# Eload_Gen_3_Power_Module.net
KiCad netlist of a schematic drawn in Altium Designer
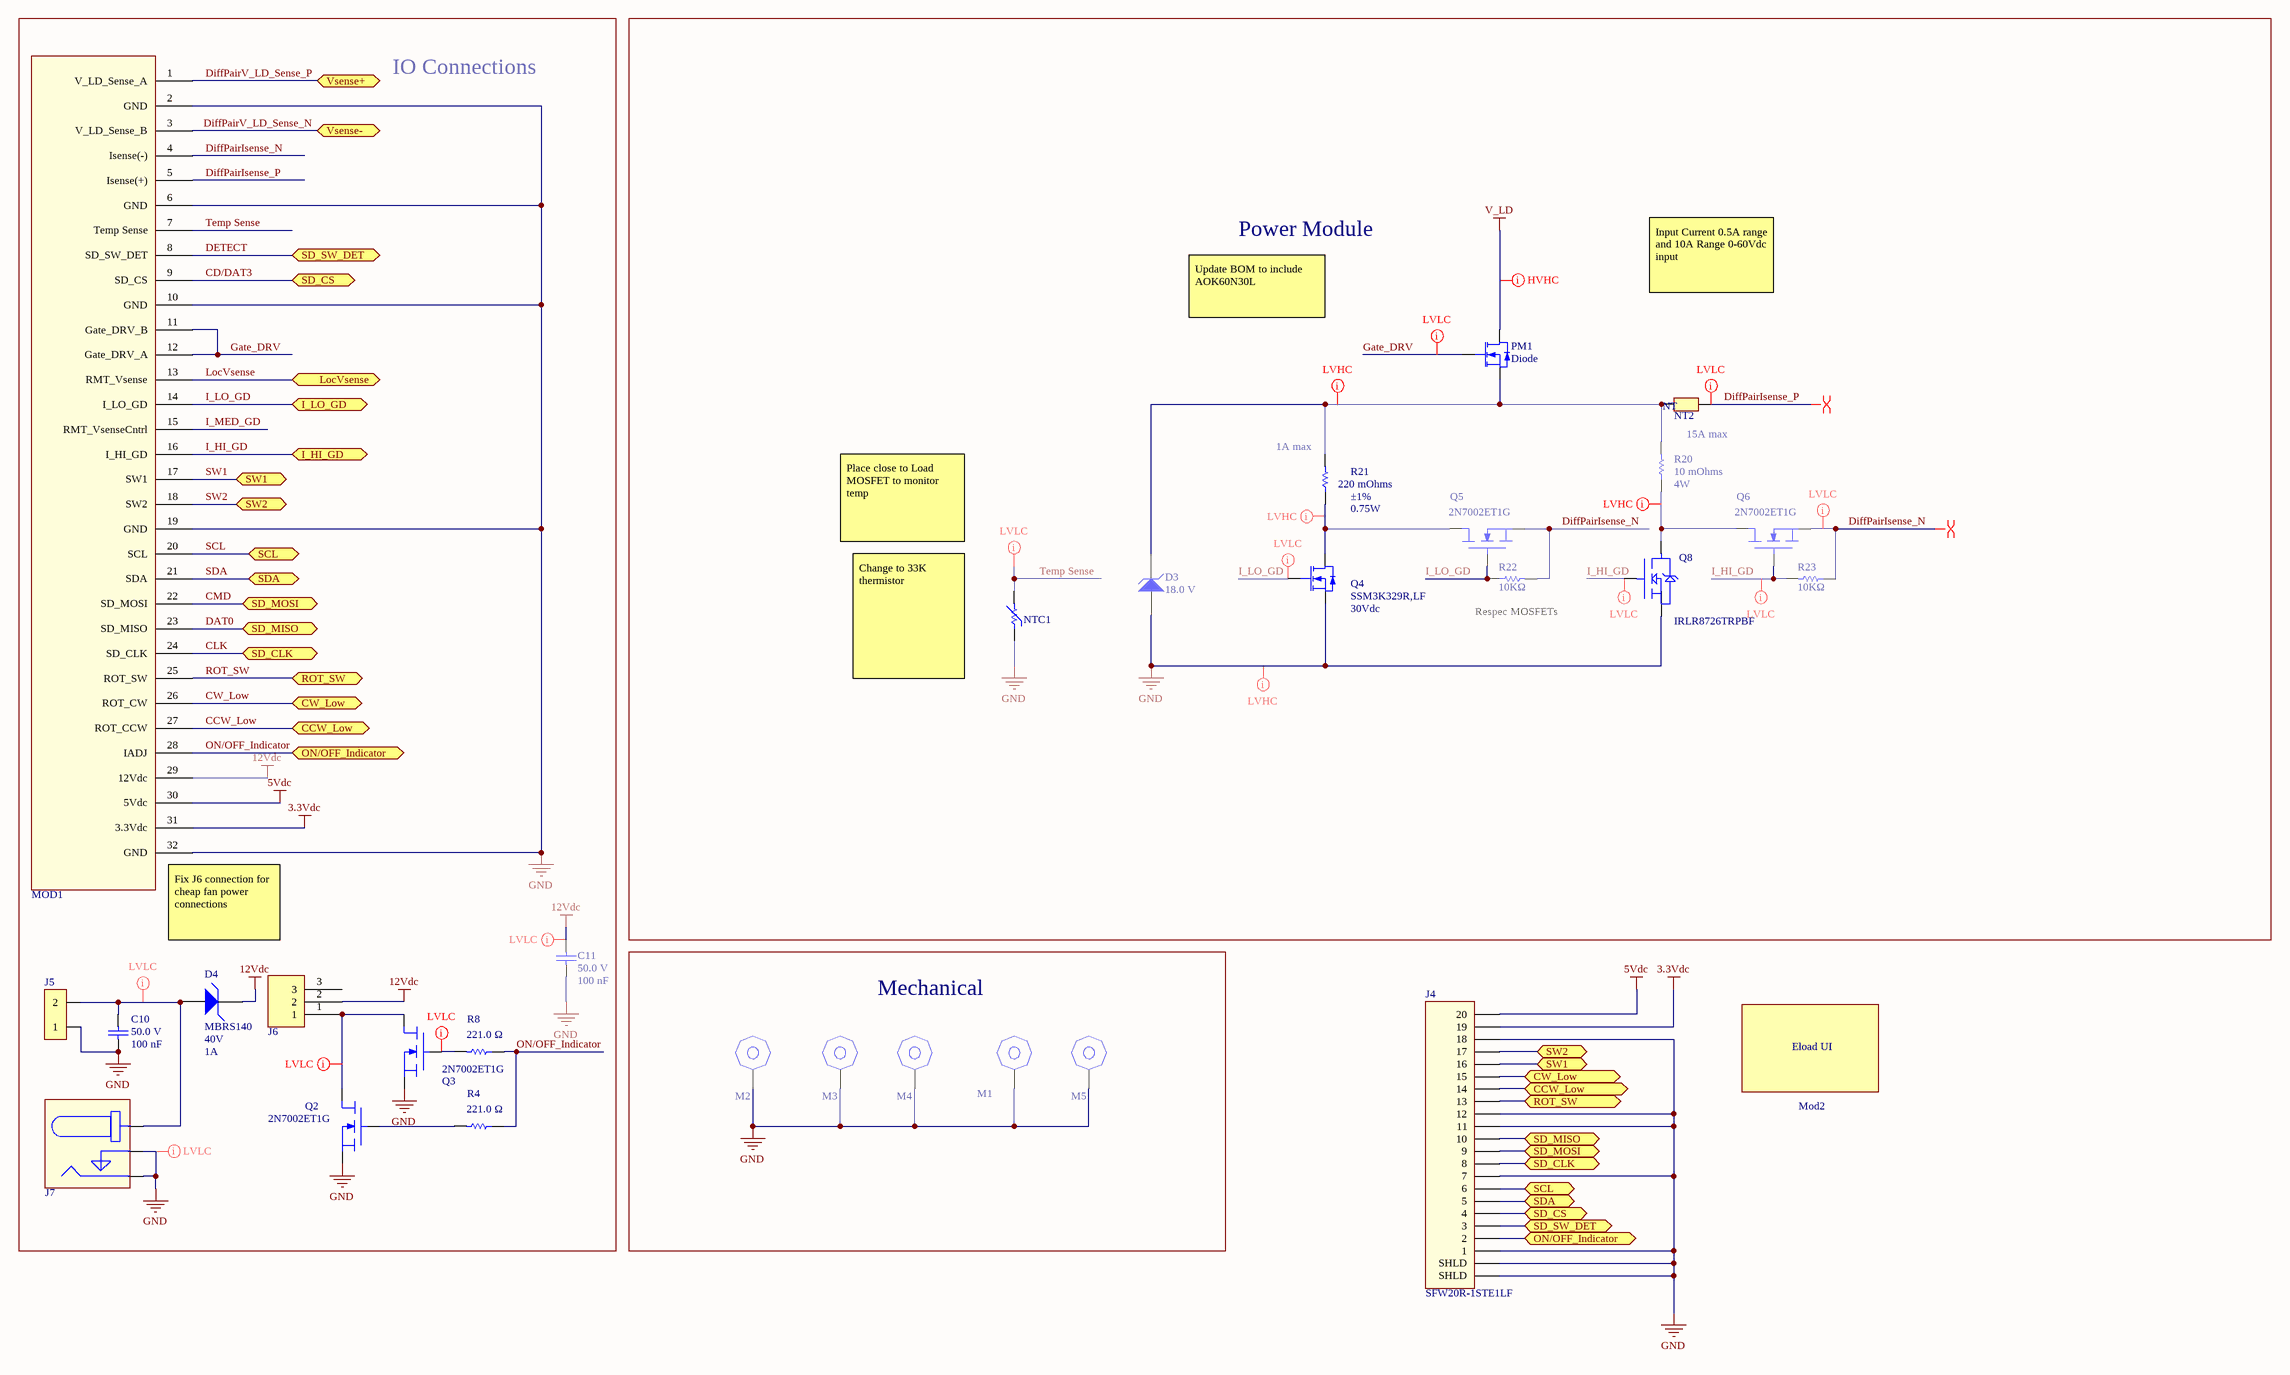
[diagram p0: Eload Gen 3 Power Module.SchDoc]

(export (version "E")
  (design (tool "Eeschema 10.0.6"))
  (components
    (comp (ref "C10")
      (value "08055C104JAT2A")
      (footprint "Cap,0805")
      (description "Capacitor; Ceramic; Cap 0.1 uF; Tol 5%; Vol-Rtg 50 VDC; SMT; 0805; X7R; Tape & Reel")
      (fields (field (name "VOLTAGE RATING (DC)") "50.0 V") (field (name "CAPACITANCE") "100 nF"))
      (libsource (lib "Master JULY2019") (part "Cap,0805,100nf,50V,5%,08055C104JAT2A"))
    )
    (comp (ref "C11")
      (value "08055C104JAT2A")
      (footprint "Cap,0805")
      (description "Capacitor; Ceramic; Cap 0.1 uF; Tol 5%; Vol-Rtg 50 VDC; SMT; 0805; X7R; Tape & Reel")
      (fields (field (name "VOLTAGE RATING (DC)") "50.0 V") (field (name "CAPACITANCE") "100 nF"))
      (libsource (lib "Master JULY2019") (part "Cap,0805,100nf,50V,5%,08055C104JAT2A"))
    )
    (comp (ref "D3")
      (value "MMSZ4705T1G")
      (footprint "SOD123")
      (description "Zener Diode 18V 500mW ±5% Surface Mount SOD-123")
      (fields (field (name "MANUFACTURER") "ON Semiconductor") (field (name "VOLTAGE RATING (DC)") "18.0 V"))
      (libsource (lib "Master JULY2019") (part "diode,Zener, 18V,500mW, SOD123,MMSZ4705T1G"))
    )
    (comp (ref "D4")
      (value "MBRS140")
      (footprint "DO214AA")
      (description "DIODE SCHOTTKY 40V 1A SMB")
      (fields
        (field (name "MANUFACTURER") "ON Semiconductor")
        (field (name "MFG P/N") "MBRS140")
        (field (name "VOLTAGE - DC REVERSE (VR) (MAX)") "40V")
        (field (name "CURRENT - AVERAGE RECTIFIED (IO)") "1A")
      )
      (libsource (lib "Master JULY2019") (part "Diode,Schottky,40V,1A,SMB,MBRS140"))
    )
    (comp (ref "J4")
      (value "SFW20R-1STE1LF")
      (footprint "Connector,FlatFlex,20Pin,RA")
      (description "CONN FFC BOTTOM 20POS 1.00MM R/A")
      (fields (field (name "MANUFACTURER") "Amphenol ICC (FCI)"))
      (libsource (lib "Master JULY2019") (part "Connector,FFC,SMD,20Pin,1mmSpc,SFW20R-1STE1LF"))
    )
    (comp (ref "J5")
      (value "TE Connectivity 282836-2")
      (footprint "TERM BLOCK 2POS SIDE ENTRY 5MM")
      (description "Wire to Board 2 Position 5 mm Pitch 30-16 AWG Euro Style Terminal Block")
      (fields (field (name "MANUFACTURER PART NUMBER") "282836-2"))
      (libsource (lib "Master JULY2019") (part "TERM BLOCK 2POS SIDE ENTRY 5MM, 282836-2"))
    )
    (comp (ref "J6")
      (value "2-644861-3")
      (footprint "Connector,TE,3-Pin,Male,Vert,2-644861-3")
      (description "Connector Header Through Hole 3 position 0.100\" (2.54mm)")
      (libsource (lib "Master JULY2019") (part "Conntector, though hole, TE, 3pin, 2.54mm,2-644861-3"))
    )
    (comp (ref "J7")
      (value "PJ-002A")
      (footprint "Connector,Barrel,2.1mm,5.5mm,DC power Jack")
      (description "Power Barrel Connector Jack 2.10mm ID (0.083\"), 5.50mm OD (0.217\") Through Hole, Right Angle")
      (fields (field (name "MANUFACTURER") "CUI Inc."))
      (libsource (lib "Master JULY2019") (part "Connector,Barrel,ID 2.1mm,OD 5.5mm,Power Connect, PJ-002A"))
    )
    (comp (ref "M1")
      (value "M3 hex Standoff")
      (footprint "Standoff,Hex,M3,8mm")
      (description "HEX STANDOFF M3,generic")
      (libsource (lib "Master Oct28_2018") (part "Standoff, M3, Hex"))
    )
    (comp (ref "M2")
      (value "M3 hex Standoff")
      (footprint "Standoff,Hex,M3,8mm")
      (description "HEX STANDOFF M3,generic")
      (libsource (lib "Master Oct28_2018") (part "Standoff, M3, Hex"))
    )
    (comp (ref "M3")
      (value "M3 hex Standoff")
      (footprint "Standoff,Hex,M3,8mm")
      (description "HEX STANDOFF M3,generic")
      (libsource (lib "Master Oct28_2018") (part "Standoff, M3, Hex"))
    )
    (comp (ref "M4")
      (value "M3 hex Standoff")
      (footprint "Standoff,Hex,M3,8mm")
      (description "HEX STANDOFF M3,generic")
      (libsource (lib "Master Oct28_2018") (part "Standoff, M3, Hex"))
    )
    (comp (ref "M5")
      (value "M3 hex Standoff")
      (footprint "Standoff,Hex,M3,8mm")
      (description "HEX STANDOFF M3,generic")
      (libsource (lib "Master Oct28_2018") (part "Standoff, M3, Hex"))
    )
    (comp (ref "MOD1")
      (value "Support PCBA")
      (footprint "Mod,ELoad Gen 3 Rev 1 Support")
      (description "Mod,Eload Gen 3 Control rev 1")
      (libsource (lib "Master JULY2019") (part "Mod,Eload Gen 3 Control rev 1"))
    )
    (comp (ref "Mod2")
      (value "ELoad Gen 3 - User Interface - Rev 1")
      (footprint "Mod,Eload Gen 3- UI Rev 1 - Vertical")
      (description "Mod, ELoad Gen 3 - User Interface - Rev 1")
      (libsource (lib "Master JULY2019") (part "Mod,Eload Gen 3 - USER INTERFACE - Rev 1"))
    )
    (comp (ref "NT2")
      (value "Net Tie,0.254mm")
      (footprint "0.254mm Net Tie")
      (libsource (lib "Master Mar2021") (part "Net Tie,0.254mm"))
    )
    (comp (ref "NTC1")
      (value "NTCLE100E3333JB0")
      (footprint "NTC,TH,2.54mm Lead Spacing,NTCLE100E3103JT2 -RA")
      (description "THERMISTOR NTC 33KOHM 4090K BEAD")
      (fields (field (name "MANUFACTURER") "Vishay BC Components"))
      (libsource (lib "Master JULY2019") (part "Sensor,Temp,NTC,33Kohm,±1.5%, NTCLE100E3333JB0"))
    )
    (comp (ref "PM1")
      (value "Diode")
      (footprint "Mod,Single TO-247-RA Horizontal CPU Cooler - LGBracket")
      (description "Singal RA Mosfet TO-247 with CPU cooler")
      (libsource (lib "Master JULY2019") (part "MOD, Singal Mosfet with Heatsink"))
    )
    (comp (ref "Q2")
      (value "2N7002ET1G")
      (footprint "SOT23-3")
      (description "Small Signal MOSFET, 60 V, 310 mA, Single, N-Channel, 3-Pin SOT-23, Pb-Free, Tape and Reel")
      (fields
        (field (name "MANUFACTURER") "ON Semiconductor")
        (field (name "MANUFACTURER PART NUMBER") "2N7002ET1G")
      )
      (libsource (lib "Master Mar2021") (part "MOSFET,N-Channel,SOT23,0.25A,60V,2N7002ET1G"))
    )
    (comp (ref "Q3")
      (value "2N7002ET1G")
      (footprint "SOT23-3")
      (description "Small Signal MOSFET, 60 V, 310 mA, Single, N-Channel, 3-Pin SOT-23, Pb-Free, Tape and Reel")
      (fields
        (field (name "MANUFACTURER") "ON Semiconductor")
        (field (name "MANUFACTURER PART NUMBER") "2N7002ET1G")
      )
      (libsource (lib "Master Mar2021") (part "MOSFET,N-Channel,SOT23,0.25A,60V,2N7002ET1G"))
    )
    (comp (ref "Q4")
      (value "SSM3K329R,LF")
      (footprint "SOT23-3")
      (description "N-Channel 30V 3.5A (Ta) 1W (Ta) Surface Mount SOT-23F")
      (fields (field (name "DRAIN TO SOURCE VOLTAGE (VDSS)") "30Vdc") (field (name "MFG P/N") "SSM3K329R,LF"))
      (libsource (lib "Master JUL_2019-Shawn") (part "MOSFET.N-Chan, SOT-23-3,3.5A,30V,1W,SSM3K329R,LF"))
    )
    (comp (ref "Q5")
      (value "2N7002ET1G")
      (footprint "SOT23-3")
      (description "Small Signal MOSFET, 60 V, 310 mA, Single, N-Channel, 3-Pin SOT-23, Pb-Free, Tape and Reel")
      (fields
        (field (name "MANUFACTURER") "ON Semiconductor")
        (field (name "MANUFACTURER PART NUMBER") "2N7002ET1G")
      )
      (libsource (lib "Master JULY2019") (part "MOSFET,N-Channel,SOT23,0.25A,60V,2N7002ET1G"))
    )
    (comp (ref "Q6")
      (value "2N7002ET1G")
      (footprint "SOT23-3")
      (description "Small Signal MOSFET, 60 V, 310 mA, Single, N-Channel, 3-Pin SOT-23, Pb-Free, Tape and Reel")
      (fields
        (field (name "MANUFACTURER") "ON Semiconductor")
        (field (name "MANUFACTURER PART NUMBER") "2N7002ET1G")
      )
      (libsource (lib "Master JULY2019") (part "MOSFET,N-Channel,SOT23,0.25A,60V,2N7002ET1G"))
    )
    (comp (ref "Q8")
      (value "IRLR8726TRPBF")
      (footprint "DPAK,3-Leads")
      (description "N-Channel 30V 86A (Tc) 75W (Tc) Surface Mount D-Pak")
      (fields (field (name "MANUFACTURER") "Infineon Technologies") (field (name "MFG P/N") "IRLR8726TRPBF"))
      (libsource (lib "Master JULY2019") (part "MOSFET, N-Chan, Dpak, 30V, 86A, 75W, IRLR8726TRPBF"))
    )
    (comp (ref "R4")
      (value "Vishay Dale CRCW0805221RFKTA")
      (footprint "res, 0805, HD")
      (description "RES SMD 221 OHM 1% 1/8W 0805")
      (fields (field (name "RESISTANCE") "221.0 Ω"))
      (libsource (lib "Master JULY2019") (part "Res,0805,221Ω,1%,100ppm,CRCW0805221RFKTA"))
    )
    (comp (ref "R8")
      (value "Vishay Dale CRCW0805221RFKTA")
      (footprint "res, 0805, HD")
      (description "RES SMD 221 OHM 1% 1/8W 0805")
      (fields (field (name "RESISTANCE") "221.0 Ω"))
      (libsource (lib "Master JULY2019") (part "Res,0805,221Ω,1%,100ppm,CRCW0805221RFKTA"))
    )
    (comp (ref "R20")
      (value "CSSH2728FT10L0")
      (footprint "Res,2827,4W")
      (fields
        (field (name "RESISTANCE") "10 mOhms")
        (field (name "TOLERANCE") "±1%")
        (field (name "POWER (WATTS)") "4W")
      )
      (libsource (lib "Master JULY2019") (part "Res,2827,shunt,10mΩ,1%,15ppm,CSSH2728FT10L0"))
    )
    (comp (ref "R21")
      (value "KRL1632E-M-R220-F-T5")
      (footprint "Res,1206")
      (description "RES 0.22 OHM 1% 3/4W 1206")
      (fields
        (field (name "MANUFACTURER") "Susumu")
        (field (name "RESISTANCE") "220 mOhms")
        (field (name "TOLERANCE") "±1%")
        (field (name "POWER (WATTS)") "0.75W")
      )
      (libsource (lib "Master JULY2019") (part "Res,1206,0.22Ohm,1%,0.75W,50ppm,KRL1632E-M-R220-F-T5"))
    )
    (comp (ref "R22")
      (value "Vishay / Dale CRCW080510K0FKTA")
      (footprint "res, 0805, HD")
      (description "RES SMD 10K OHM 1% 1/8W 0805")
      (fields (field (name "RESISTANCE") "10KΩ"))
      (libsource (lib "Master JULY2019") (part "Res,0805,10.0kΩ,1%,100 ppm,CRCW080510K0FKTA"))
    )
    (comp (ref "R23")
      (value "Vishay / Dale CRCW080510K0FKTA")
      (footprint "res, 0805, HD")
      (description "RES SMD 10K OHM 1% 1/8W 0805")
      (fields (field (name "RESISTANCE") "10KΩ"))
      (libsource (lib "Master JULY2019") (part "Res,0805,10.0kΩ,1%,100 ppm,CRCW080510K0FKTA"))
    )
  )
  (nets
    (net (code "1") (name "/CCW_Low") (class "Default")
      (node (ref "J4") (pin "14") (pinfunction "14_14") (pintype "passive"))
      (node (ref "MOD1") (pin "27") (pinfunction "ROT_CCW_27") (pintype "passive"))
    )
    (net (code "2") (name "/CD{slash}DAT3") (class "Default")
      (node (ref "J4") (pin "4") (pinfunction "4_4") (pintype "passive"))
      (node (ref "MOD1") (pin "9") (pinfunction "SD_CS_9") (pintype "passive"))
    )
    (net (code "3") (name "/CLK") (class "Default")
      (node (ref "J4") (pin "8") (pinfunction "8_8") (pintype "passive"))
      (node (ref "MOD1") (pin "24") (pinfunction "SD_CLK_24") (pintype "passive"))
    )
    (net (code "4") (name "/CMD") (class "Default")
      (node (ref "J4") (pin "9") (pinfunction "9_9") (pintype "passive"))
      (node (ref "MOD1") (pin "22") (pinfunction "SD_MOSI_22") (pintype "passive"))
    )
    (net (code "5") (name "/CW_Low") (class "Default")
      (node (ref "J4") (pin "15") (pinfunction "15_15") (pintype "passive"))
      (node (ref "MOD1") (pin "26") (pinfunction "ROT_CW_26") (pintype "passive"))
    )
    (net (code "6") (name "/DAT0") (class "Default")
      (node (ref "J4") (pin "10") (pinfunction "10_10") (pintype "passive"))
      (node (ref "MOD1") (pin "23") (pinfunction "SD_MISO_23") (pintype "passive"))
    )
    (net (code "7") (name "/DETECT") (class "Default")
      (node (ref "J4") (pin "3") (pinfunction "3_3") (pintype "passive"))
      (node (ref "MOD1") (pin "8") (pinfunction "SD_SW_DET_8") (pintype "passive"))
    )
    (net (code "8") (name "/DiffPairIsense_N") (class "Default")
      (node (ref "MOD1") (pin "4") (pinfunction "Isense(-)_4") (pintype "passive"))
      (node (ref "Q5") (pin "2") (pinfunction "S_2") (pintype "passive"))
      (node (ref "Q6") (pin "2") (pinfunction "S_2") (pintype "passive"))
      (node (ref "R22") (pin "2") (pinfunction "2_2") (pintype "passive"))
      (node (ref "R23") (pin "1") (pinfunction "1_1") (pintype "passive"))
    )
    (net (code "9") (name "/DiffPairIsense_P") (class "Default")
      (node (ref "MOD1") (pin "5") (pinfunction "Isense(+)_5") (pintype "passive"))
      (node (ref "NT2") (pin "2") (pinfunction "2_2") (pintype "passive"))
    )
    (net (code "10") (name "/DiffPairV_LD_Sense_N") (class "Default")
      (node (ref "MOD1") (pin "3") (pinfunction "V_LD_Sense_B_3") (pintype "passive"))
    )
    (net (code "11") (name "/DiffPairV_LD_Sense_P") (class "Default")
      (node (ref "MOD1") (pin "1") (pinfunction "V_LD_Sense_A_1") (pintype "passive"))
    )
    (net (code "12") (name "/Gate_DRV") (class "Default")
      (node (ref "MOD1") (pin "11") (pinfunction "Gate_DRV_B_11") (pintype "passive"))
      (node (ref "MOD1") (pin "12") (pinfunction "Gate_DRV_A_12") (pintype "passive"))
      (node (ref "PM1") (pin "1") (pinfunction "G_1") (pintype "passive"))
    )
    (net (code "13") (name "/I_HI_GD") (class "Default")
      (node (ref "MOD1") (pin "16") (pinfunction "I_HI_GD_16") (pintype "passive"))
      (node (ref "Q6") (pin "1") (pinfunction "G_1") (pintype "passive"))
      (node (ref "Q8") (pin "1") (pinfunction "Gate_1") (pintype "passive"))
      (node (ref "R23") (pin "2") (pinfunction "2_2") (pintype "passive"))
    )
    (net (code "14") (name "/I_LO_GD") (class "Default")
      (node (ref "MOD1") (pin "14") (pinfunction "I_LO_GD_14") (pintype "passive"))
      (node (ref "Q4") (pin "1") (pinfunction "G_1") (pintype "passive"))
      (node (ref "Q5") (pin "1") (pinfunction "G_1") (pintype "passive"))
      (node (ref "R22") (pin "1") (pinfunction "1_1") (pintype "passive"))
    )
    (net (code "15") (name "/I_MED_GD") (class "Default")
      (node (ref "MOD1") (pin "15") (pinfunction "RMT_VsenseCntrl_15") (pintype "passive"))
    )
    (net (code "16") (name "/LocVsense") (class "Default")
      (node (ref "MOD1") (pin "13") (pinfunction "RMT_Vsense_13") (pintype "passive"))
    )
    (net (code "17") (name "/ON{slash}OFF_Indicator") (class "Default")
      (node (ref "J4") (pin "2") (pinfunction "2_2") (pintype "passive"))
      (node (ref "MOD1") (pin "28") (pinfunction "IADJ_28") (pintype "passive"))
      (node (ref "R4") (pin "1") (pinfunction "1_1") (pintype "passive"))
      (node (ref "R8") (pin "1") (pinfunction "1_1") (pintype "passive"))
    )
    (net (code "18") (name "/ROT_SW") (class "Default")
      (node (ref "J4") (pin "13") (pinfunction "13_13") (pintype "passive"))
      (node (ref "MOD1") (pin "25") (pinfunction "ROT_SW_25") (pintype "passive"))
    )
    (net (code "19") (name "/SCL") (class "Default")
      (node (ref "J4") (pin "6") (pinfunction "6_6") (pintype "passive"))
      (node (ref "MOD1") (pin "20") (pinfunction "SCL_20") (pintype "passive"))
    )
    (net (code "20") (name "/SDA") (class "Default")
      (node (ref "J4") (pin "5") (pinfunction "5_5") (pintype "passive"))
      (node (ref "MOD1") (pin "21") (pinfunction "SDA_21") (pintype "passive"))
    )
    (net (code "21") (name "/SW1") (class "Default")
      (node (ref "J4") (pin "16") (pinfunction "16_16") (pintype "passive"))
      (node (ref "MOD1") (pin "17") (pinfunction "SW1_17") (pintype "passive"))
    )
    (net (code "22") (name "/SW2") (class "Default")
      (node (ref "J4") (pin "17") (pinfunction "17_17") (pintype "passive"))
      (node (ref "MOD1") (pin "18") (pinfunction "SW2_18") (pintype "passive"))
    )
    (net (code "23") (name "/Temp Sense") (class "Default")
      (node (ref "MOD1") (pin "7") (pinfunction "Temp_Sense_7") (pintype "passive"))
      (node (ref "NTC1") (pin "2") (pinfunction "2_2") (pintype "passive"))
    )
    (net (code "24") (name "3.3Vdc") (class "Default")
      (node (ref "J4") (pin "19") (pinfunction "19_19") (pintype "passive"))
      (node (ref "MOD1") (pin "31") (pinfunction "3.3Vdc_31") (pintype "passive"))
    )
    (net (code "25") (name "5Vdc") (class "Default")
      (node (ref "J4") (pin "20") (pinfunction "20_20") (pintype "passive"))
      (node (ref "MOD1") (pin "30") (pinfunction "5Vdc_30") (pintype "passive"))
    )
    (net (code "26") (name "12Vdc") (class "Default")
      (node (ref "C11") (pin "2") (pinfunction "2_2") (pintype "passive"))
      (node (ref "D4") (pin "2") (pinfunction "2_2") (pintype "passive"))
      (node (ref "J6") (pin "2") (pinfunction "2_2") (pintype "passive"))
      (node (ref "MOD1") (pin "29") (pinfunction "12Vdc_29") (pintype "passive"))
    )
    (net (code "27") (name "GND") (class "Default")
      (node (ref "C10") (pin "1") (pinfunction "1_1") (pintype "passive"))
      (node (ref "C11") (pin "1") (pinfunction "1_1") (pintype "passive"))
      (node (ref "D3") (pin "2") (pinfunction "A_2") (pintype "passive"))
      (node (ref "J4") (pin "1") (pinfunction "1_1") (pintype "passive"))
      (node (ref "J4") (pin "11") (pinfunction "11_11") (pintype "passive"))
      (node (ref "J4") (pin "12") (pinfunction "12_12") (pintype "passive"))
      (node (ref "J4") (pin "18") (pinfunction "18_18") (pintype "passive"))
      (node (ref "J4") (pin "21") (pinfunction "SHLD_21") (pintype "passive"))
      (node (ref "J4") (pin "22") (pinfunction "SHLD_22") (pintype "passive"))
      (node (ref "J4") (pin "7") (pinfunction "7_7") (pintype "passive"))
      (node (ref "J5") (pin "1") (pinfunction "1_1") (pintype "passive"))
      (node (ref "J7") (pin "2") (pinfunction "2_2") (pintype "passive"))
      (node (ref "J7") (pin "3") (pinfunction "3_3") (pintype "passive"))
      (node (ref "M1") (pin "0") (pinfunction "0_0") (pintype "passive"))
      (node (ref "M2") (pin "0") (pinfunction "0_0") (pintype "passive"))
      (node (ref "M3") (pin "0") (pinfunction "0_0") (pintype "passive"))
      (node (ref "M4") (pin "0") (pinfunction "0_0") (pintype "passive"))
      (node (ref "M5") (pin "0") (pinfunction "0_0") (pintype "passive"))
      (node (ref "MOD1") (pin "10") (pinfunction "GND_10") (pintype "passive"))
      (node (ref "MOD1") (pin "19") (pinfunction "GND_19") (pintype "passive"))
      (node (ref "MOD1") (pin "2") (pinfunction "GND_2") (pintype "passive"))
      (node (ref "MOD1") (pin "32") (pinfunction "GND_32") (pintype "passive"))
      (node (ref "MOD1") (pin "6") (pinfunction "GND_6") (pintype "passive"))
      (node (ref "NTC1") (pin "1") (pinfunction "1_1") (pintype "passive"))
      (node (ref "Q2") (pin "2") (pinfunction "S_2") (pintype "passive"))
      (node (ref "Q3") (pin "2") (pinfunction "S_2") (pintype "passive"))
      (node (ref "Q4") (pin "2") (pinfunction "S_2") (pintype "passive"))
      (node (ref "Q8") (pin "2") (pinfunction "Gate_2") (pintype "passive"))
    )
    (net (code "28") (name "Net-(C10-Pad2)") (class "Default")
      (node (ref "C10") (pin "2") (pinfunction "2_2") (pintype "passive"))
      (node (ref "D4") (pin "1") (pinfunction "1_1") (pintype "passive"))
      (node (ref "J5") (pin "2") (pinfunction "2_2") (pintype "passive"))
      (node (ref "J7") (pin "1") (pinfunction "1_1") (pintype "passive"))
    )
    (net (code "29") (name "Net-(D3-K)") (class "Default")
      (node (ref "D3") (pin "1") (pinfunction "K_1") (pintype "passive"))
      (node (ref "NT2") (pin "1") (pinfunction "1_1") (pintype "passive"))
      (node (ref "PM1") (pin "3") (pinfunction "S_3") (pintype "passive"))
      (node (ref "R20") (pin "2") (pinfunction "2_2") (pintype "passive"))
      (node (ref "R21") (pin "2") (pinfunction "2_2") (pintype "passive"))
    )
    (net (code "30") (name "Net-(Q2-D)") (class "Default")
      (node (ref "J6") (pin "1") (pinfunction "1_1") (pintype "passive"))
      (node (ref "Q2") (pin "3") (pinfunction "D_3") (pintype "passive"))
      (node (ref "Q3") (pin "3") (pinfunction "D_3") (pintype "passive"))
    )
    (net (code "31") (name "Net-(Q2-G)") (class "Default")
      (node (ref "Q2") (pin "1") (pinfunction "G_1") (pintype "passive"))
      (node (ref "R4") (pin "2") (pinfunction "2_2") (pintype "passive"))
    )
    (net (code "32") (name "Net-(Q3-G)") (class "Default")
      (node (ref "Q3") (pin "1") (pinfunction "G_1") (pintype "passive"))
      (node (ref "R8") (pin "2") (pinfunction "2_2") (pintype "passive"))
    )
    (net (code "33") (name "Net-(Q4-D)") (class "Default")
      (node (ref "Q4") (pin "3") (pinfunction "D_3") (pintype "passive"))
      (node (ref "Q5") (pin "3") (pinfunction "D_3") (pintype "passive"))
      (node (ref "R21") (pin "1") (pinfunction "1_1") (pintype "passive"))
    )
    (net (code "34") (name "Net-(Q6-D)") (class "Default")
      (node (ref "Q6") (pin "3") (pinfunction "D_3") (pintype "passive"))
      (node (ref "Q8") (pin "3") (pinfunction "Gate_3") (pintype "passive"))
      (node (ref "R20") (pin "1") (pinfunction "1_1") (pintype "passive"))
    )
    (net (code "35") (name "V_LD") (class "Default")
      (node (ref "PM1") (pin "2") (pinfunction "D_2") (pintype "passive"))
    )
    (net (code "36") (name "unconnected-(J6-Pad3)") (class "Default")
      (node (ref "J6") (pin "3") (pinfunction "3_3") (pintype "passive"))
    )
  )
)
